# ESC_C.net
KiCad netlist of a schematic drawn in Altium Designer
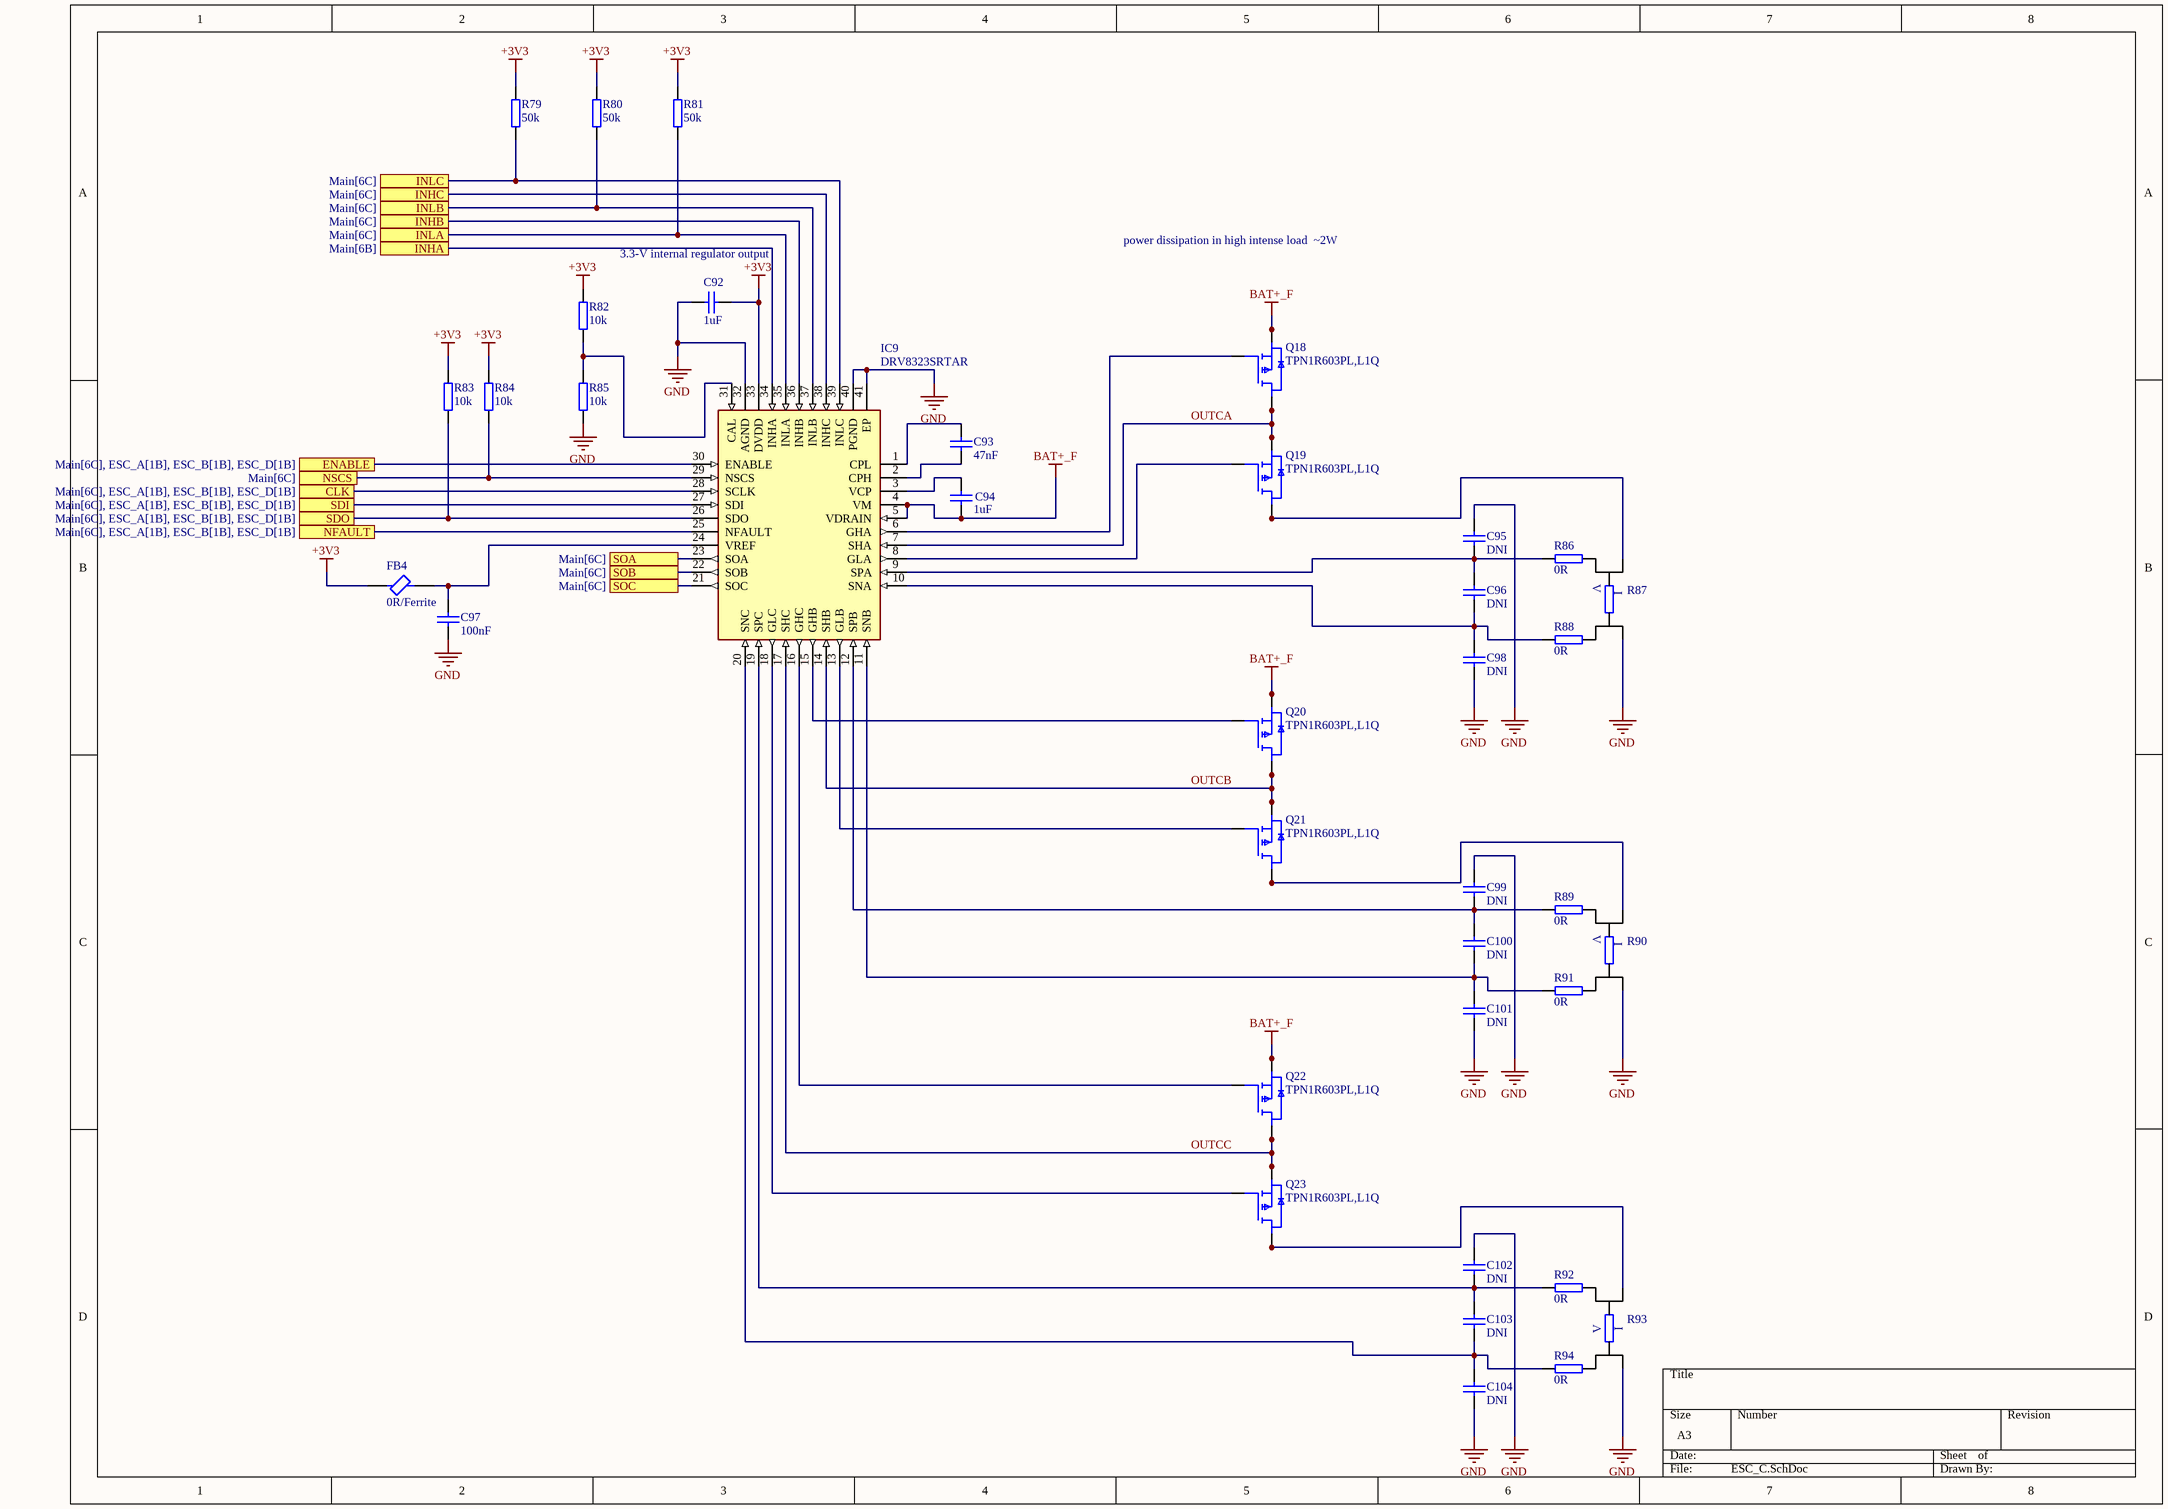
[diagram p0: ESC_C.SchDoc]

(export (version "E")
  (design (tool "Eeschema 10.0.6"))
  (components
    (comp (ref "C92")
      (value "1uF")
      (footprint "CAP0402")
      (fields
        (field (name "VOLTAGE") "50V")
        (field (name "MANUFACTURER_PART_NUMBER") "GRM155R61H105KE05J")
        (field (name "Comment") "Cap0402")
      )
      (libsource (lib "capacitorsSMD") (part "Cap0402"))
    )
    (comp (ref "C93")
      (value "47nF")
      (footprint "CAP0603")
      (description "50V")
      (fields (field (name "Comment") "Cap0603") (field (name "PUBLISHER") "Altium Limited"))
      (libsource (lib "capacitorsSMD") (part "CapSMD0603"))
    )
    (comp (ref "C94")
      (value "1uF")
      (footprint "CAP0603")
      (description "50V")
      (fields (field (name "Comment") "Cap0603") (field (name "PUBLISHER") "Altium Limited"))
      (libsource (lib "capacitorsSMD") (part "CapSMD0603"))
    )
    (comp (ref "C95")
      (value "DNI")
      (footprint "CAP0402")
      (fields (field (name "Comment") "Cap0402"))
      (libsource (lib "capacitorsSMD") (part "Cap0402"))
    )
    (comp (ref "C96")
      (value "DNI")
      (footprint "CAP0402")
      (fields (field (name "Comment") "Cap0402"))
      (libsource (lib "capacitorsSMD") (part "Cap0402"))
    )
    (comp (ref "C97")
      (value "100nF")
      (footprint "CAP0402")
      (fields
        (field (name "VOLTAGE") "50V")
        (field (name "MANUFACTURER_PART_NUMBER") "GRM155R71H104ME14D")
        (field (name "Comment") "Cap0402")
      )
      (libsource (lib "capacitorsSMD") (part "Cap0402"))
    )
    (comp (ref "C98")
      (value "DNI")
      (footprint "CAP0402")
      (fields (field (name "Comment") "Cap0402"))
      (libsource (lib "capacitorsSMD") (part "Cap0402"))
    )
    (comp (ref "C99")
      (value "DNI")
      (footprint "CAP0402")
      (fields (field (name "Comment") "Cap0402"))
      (libsource (lib "capacitorsSMD") (part "Cap0402"))
    )
    (comp (ref "C100")
      (value "DNI")
      (footprint "CAP0402")
      (fields (field (name "Comment") "Cap0402"))
      (libsource (lib "capacitorsSMD") (part "Cap0402"))
    )
    (comp (ref "C101")
      (value "DNI")
      (footprint "CAP0402")
      (fields (field (name "Comment") "Cap0402"))
      (libsource (lib "capacitorsSMD") (part "Cap0402"))
    )
    (comp (ref "C102")
      (value "DNI")
      (footprint "CAP0402")
      (fields (field (name "Comment") "Cap0402"))
      (libsource (lib "capacitorsSMD") (part "Cap0402"))
    )
    (comp (ref "C103")
      (value "DNI")
      (footprint "CAP0402")
      (fields (field (name "Comment") "Cap0402"))
      (libsource (lib "capacitorsSMD") (part "Cap0402"))
    )
    (comp (ref "C104")
      (value "DNI")
      (footprint "CAP0402")
      (fields (field (name "Comment") "Cap0402"))
      (libsource (lib "capacitorsSMD") (part "Cap0402"))
    )
    (comp (ref "FB4")
      (value "0R/Ferrite")
      (footprint "SamacSys:NFZ15SG152SN10B")
      (description "Ferrite Bead")
      (fields
        (field (name "MANUFACTURER_PART_NUMBER") "BLM15PE471SH1D")
        (field (name "MOUSER PART NUMBER") "81-BLM15PE471SH1D")
      )
      (libsource (lib "SamacSys") (part "BLM15PE471SH1D"))
    )
    (comp (ref "IC9")
      (value "DRV8323SRTAR")
      (footprint "SamacSys:QFN50P600X600X80-41N-D")
      (description "Integrated Circuit")
      (fields (field (name "MOUSER PART NUMBER") "595-DRV8323SRTAR"))
      (libsource (lib "*") (part "DRV8323SRTAR"))
    )
    (comp (ref "Q18")
      (value "TPN1R603PL,L1Q")
      (footprint "SamacSys:TPN1R603PLL1Q")
      (description "MOSFET (N-Channel)")
      (fields (field (name "MOUSER PART NUMBER") "757-TPN1R603PLL1Q"))
      (libsource (lib "SamacSys") (part "TPN1R603PL,L1Q"))
    )
    (comp (ref "Q19")
      (value "TPN1R603PL,L1Q")
      (footprint "SamacSys:TPN1R603PLL1Q")
      (description "MOSFET (N-Channel)")
      (fields (field (name "MOUSER PART NUMBER") "757-TPN1R603PLL1Q"))
      (libsource (lib "SamacSys") (part "TPN1R603PL,L1Q"))
    )
    (comp (ref "Q20")
      (value "TPN1R603PL,L1Q")
      (footprint "SamacSys:TPN1R603PLL1Q")
      (description "MOSFET (N-Channel)")
      (fields (field (name "MOUSER PART NUMBER") "757-TPN1R603PLL1Q"))
      (libsource (lib "SamacSys") (part "TPN1R603PL,L1Q"))
    )
    (comp (ref "Q21")
      (value "TPN1R603PL,L1Q")
      (footprint "SamacSys:TPN1R603PLL1Q")
      (description "MOSFET (N-Channel)")
      (fields (field (name "MOUSER PART NUMBER") "757-TPN1R603PLL1Q"))
      (libsource (lib "SamacSys") (part "TPN1R603PL,L1Q"))
    )
    (comp (ref "Q22")
      (value "TPN1R603PL,L1Q")
      (footprint "SamacSys:TPN1R603PLL1Q")
      (description "MOSFET (N-Channel)")
      (fields (field (name "MOUSER PART NUMBER") "757-TPN1R603PLL1Q"))
      (libsource (lib "SamacSys") (part "TPN1R603PL,L1Q"))
    )
    (comp (ref "Q23")
      (value "TPN1R603PL,L1Q")
      (footprint "SamacSys:TPN1R603PLL1Q")
      (description "MOSFET (N-Channel)")
      (fields (field (name "MOUSER PART NUMBER") "757-TPN1R603PLL1Q"))
      (libsource (lib "SamacSys") (part "TPN1R603PL,L1Q"))
    )
    (comp (ref "R79")
      (value "50k")
      (footprint "RES0402")
      (fields (field (name "MANUFACTURER_PART_NUMBER") "TNPW040249K9DEED") (field (name "Comment") "Res0402"))
      (libsource (lib "resistorSMD") (part "Res0402"))
    )
    (comp (ref "R80")
      (value "50k")
      (footprint "RES0402")
      (fields (field (name "MANUFACTURER_PART_NUMBER") "TNPW040249K9DEED") (field (name "Comment") "Res0402"))
      (libsource (lib "resistorSMD") (part "Res0402"))
    )
    (comp (ref "R81")
      (value "50k")
      (footprint "RES0402")
      (fields (field (name "MANUFACTURER_PART_NUMBER") "TNPW040249K9DEED") (field (name "Comment") "Res0402"))
      (libsource (lib "resistorSMD") (part "Res0402"))
    )
    (comp (ref "R82")
      (value "10k")
      (footprint "RES0402")
      (fields (field (name "MANUFACTURER_PART_NUMBER") "ERA-2AED103X") (field (name "Comment") "Res0402"))
      (libsource (lib "resistorSMD") (part "Res0402"))
    )
    (comp (ref "R83")
      (value "10k")
      (footprint "RES0402")
      (fields (field (name "MANUFACTURER_PART_NUMBER") "ERA-2AED103X") (field (name "Comment") "Res0402"))
      (libsource (lib "resistorSMD") (part "Res0402"))
    )
    (comp (ref "R84")
      (value "10k")
      (footprint "RES0402")
      (fields (field (name "MANUFACTURER_PART_NUMBER") "ERA-2AED103X") (field (name "Comment") "Res0402"))
      (libsource (lib "resistorSMD") (part "Res0402"))
    )
    (comp (ref "R85")
      (value "10k")
      (footprint "RES0402")
      (fields (field (name "MANUFACTURER_PART_NUMBER") "ERA-2AED103X") (field (name "Comment") "Res0402"))
      (libsource (lib "resistorSMD") (part "Res0402"))
    )
    (comp (ref "R86")
      (value "0R")
      (footprint "RES0402")
      (fields (field (name "MANUFACTURER_PART_NUMBER") "RCA04020000ZSED") (field (name "Comment") "Res0402"))
      (libsource (lib "resistorSMD") (part "Res0402"))
    )
    (comp (ref "R87")
      (value "WSK12161L000FEA")
      (footprint "SamacSys:WSK12161L000FEA")
      (description "Resistor")
      (fields
        (field (name "MANUFACTURER_PART_NUMBER") "WSK1216L5000FEA")
        (field (name "MOUSER PART NUMBER") "71-WSK1216L5000FEA")
      )
      (libsource (lib "SamacSys") (part "WSK1216L5000FEA"))
    )
    (comp (ref "R88")
      (value "0R")
      (footprint "RES0402")
      (fields (field (name "MANUFACTURER_PART_NUMBER") "RCA04020000ZSED") (field (name "Comment") "Res0402"))
      (libsource (lib "resistorSMD") (part "Res0402"))
    )
    (comp (ref "R89")
      (value "0R")
      (footprint "RES0402")
      (fields (field (name "MANUFACTURER_PART_NUMBER") "RCA04020000ZSED") (field (name "Comment") "Res0402"))
      (libsource (lib "resistorSMD") (part "Res0402"))
    )
    (comp (ref "R90")
      (value "WSK12161L000FEA")
      (footprint "SamacSys:WSK12161L000FEA")
      (description "Resistor")
      (fields
        (field (name "MANUFACTURER_PART_NUMBER") "WSK1216L5000FEA")
        (field (name "MOUSER PART NUMBER") "71-WSK1216L5000FEA")
      )
      (libsource (lib "SamacSys") (part "WSK1216L5000FEA"))
    )
    (comp (ref "R91")
      (value "0R")
      (footprint "RES0402")
      (fields (field (name "MANUFACTURER_PART_NUMBER") "RCA04020000ZSED") (field (name "Comment") "Res0402"))
      (libsource (lib "resistorSMD") (part "Res0402"))
    )
    (comp (ref "R92")
      (value "0R")
      (footprint "RES0402")
      (fields (field (name "MANUFACTURER_PART_NUMBER") "RCA04020000ZSED") (field (name "Comment") "Res0402"))
      (libsource (lib "resistorSMD") (part "Res0402"))
    )
    (comp (ref "R93")
      (value "WSK12161L000FEA")
      (footprint "SamacSys:WSK12161L000FEA")
      (description "Resistor")
      (fields
        (field (name "MANUFACTURER_PART_NUMBER") "WSK1216L5000FEA")
        (field (name "MOUSER PART NUMBER") "71-WSK1216L5000FEA")
      )
      (libsource (lib "SamacSys") (part "WSK1216L5000FEA"))
    )
    (comp (ref "R94")
      (value "0R")
      (footprint "RES0402")
      (fields (field (name "MANUFACTURER_PART_NUMBER") "RCA04020000ZSED") (field (name "Comment") "Res0402"))
      (libsource (lib "resistorSMD") (part "Res0402"))
    )
  )
  (nets
    (net (code "1") (name "+3V3") (class "Default")
      (node (ref "C92") (pin "2") (pinfunction "2_2") (pintype "passive"))
      (node (ref "FB4") (pin "1") (pinfunction "1_1") (pintype "passive"))
      (node (ref "IC9") (pin "33") (pinfunction "DVDD_33") (pintype "power_in"))
      (node (ref "R79") (pin "2") (pinfunction "2_2") (pintype "passive"))
      (node (ref "R80") (pin "2") (pinfunction "2_2") (pintype "passive"))
      (node (ref "R81") (pin "2") (pinfunction "2_2") (pintype "passive"))
      (node (ref "R82") (pin "2") (pinfunction "2_2") (pintype "passive"))
      (node (ref "R83") (pin "2") (pinfunction "2_2") (pintype "passive"))
      (node (ref "R84") (pin "2") (pinfunction "2_2") (pintype "passive"))
    )
    (net (code "2") (name "/CLK") (class "Default")
      (node (ref "IC9") (pin "28") (pinfunction "SCLK_28") (pintype "input"))
    )
    (net (code "3") (name "/ENABLE") (class "Default")
      (node (ref "IC9") (pin "30") (pinfunction "ENABLE_30") (pintype "input"))
    )
    (net (code "4") (name "/INHA") (class "Default")
      (node (ref "IC9") (pin "34") (pinfunction "INHA_34") (pintype "input"))
    )
    (net (code "5") (name "/INHB") (class "Default")
      (node (ref "IC9") (pin "36") (pinfunction "INHB_36") (pintype "input"))
    )
    (net (code "6") (name "/INHC") (class "Default")
      (node (ref "IC9") (pin "38") (pinfunction "INHC_38") (pintype "input"))
    )
    (net (code "7") (name "/INLA") (class "Default")
      (node (ref "IC9") (pin "35") (pinfunction "INLA_35") (pintype "input"))
      (node (ref "R81") (pin "1") (pinfunction "1_1") (pintype "passive"))
    )
    (net (code "8") (name "/INLB") (class "Default")
      (node (ref "IC9") (pin "37") (pinfunction "INLB_37") (pintype "input"))
      (node (ref "R80") (pin "1") (pinfunction "1_1") (pintype "passive"))
    )
    (net (code "9") (name "/INLC") (class "Default")
      (node (ref "IC9") (pin "39") (pinfunction "INLC_39") (pintype "input"))
      (node (ref "R79") (pin "1") (pinfunction "1_1") (pintype "passive"))
    )
    (net (code "10") (name "/NFAULT") (class "Default")
      (node (ref "IC9") (pin "25") (pinfunction "NFAULT_25") (pintype "passive"))
    )
    (net (code "11") (name "/NSCS") (class "Default")
      (node (ref "IC9") (pin "29") (pinfunction "NSCS_29") (pintype "input"))
      (node (ref "R84") (pin "1") (pinfunction "1_1") (pintype "passive"))
    )
    (net (code "12") (name "/OUTCA") (class "Default")
      (node (ref "IC9") (pin "7") (pinfunction "SHA_7") (pintype "input"))
      (node (ref "Q18") (pin "5") (pinfunction "D_1_5") (pintype "passive"))
      (node (ref "Q18") (pin "6") (pinfunction "D_2_6") (pintype "passive"))
      (node (ref "Q18") (pin "7") (pinfunction "D_3_7") (pintype "passive"))
      (node (ref "Q18") (pin "8") (pinfunction "D_4_8") (pintype "passive"))
      (node (ref "Q18") (pin "9") (pinfunction "D_4_9") (pintype "passive"))
      (node (ref "Q19") (pin "1") (pinfunction "S_1_1") (pintype "passive"))
      (node (ref "Q19") (pin "2") (pinfunction "S_2_2") (pintype "passive"))
      (node (ref "Q19") (pin "3") (pinfunction "S_3_3") (pintype "passive"))
    )
    (net (code "13") (name "/OUTCB") (class "Default")
      (node (ref "IC9") (pin "14") (pinfunction "SHB_14") (pintype "input"))
      (node (ref "Q20") (pin "5") (pinfunction "D_1_5") (pintype "passive"))
      (node (ref "Q20") (pin "6") (pinfunction "D_2_6") (pintype "passive"))
      (node (ref "Q20") (pin "7") (pinfunction "D_3_7") (pintype "passive"))
      (node (ref "Q20") (pin "8") (pinfunction "D_4_8") (pintype "passive"))
      (node (ref "Q20") (pin "9") (pinfunction "D_4_9") (pintype "passive"))
      (node (ref "Q21") (pin "1") (pinfunction "S_1_1") (pintype "passive"))
      (node (ref "Q21") (pin "2") (pinfunction "S_2_2") (pintype "passive"))
      (node (ref "Q21") (pin "3") (pinfunction "S_3_3") (pintype "passive"))
    )
    (net (code "14") (name "/OUTCC") (class "Default")
      (node (ref "IC9") (pin "17") (pinfunction "SHC_17") (pintype "input"))
      (node (ref "Q22") (pin "5") (pinfunction "D_1_5") (pintype "passive"))
      (node (ref "Q22") (pin "6") (pinfunction "D_2_6") (pintype "passive"))
      (node (ref "Q22") (pin "7") (pinfunction "D_3_7") (pintype "passive"))
      (node (ref "Q22") (pin "8") (pinfunction "D_4_8") (pintype "passive"))
      (node (ref "Q22") (pin "9") (pinfunction "D_4_9") (pintype "passive"))
      (node (ref "Q23") (pin "1") (pinfunction "S_1_1") (pintype "passive"))
      (node (ref "Q23") (pin "2") (pinfunction "S_2_2") (pintype "passive"))
      (node (ref "Q23") (pin "3") (pinfunction "S_3_3") (pintype "passive"))
    )
    (net (code "15") (name "/SDI") (class "Default")
      (node (ref "IC9") (pin "27") (pinfunction "SDI_27") (pintype "input"))
    )
    (net (code "16") (name "/SDO") (class "Default")
      (node (ref "IC9") (pin "26") (pinfunction "SDO_26") (pintype "passive"))
      (node (ref "R83") (pin "1") (pinfunction "1_1") (pintype "passive"))
    )
    (net (code "17") (name "/SOA") (class "Default")
      (node (ref "IC9") (pin "23") (pinfunction "SOA_23") (pintype "output"))
    )
    (net (code "18") (name "/SOB") (class "Default")
      (node (ref "IC9") (pin "22") (pinfunction "SOB_22") (pintype "output"))
    )
    (net (code "19") (name "/SOC") (class "Default")
      (node (ref "IC9") (pin "21") (pinfunction "SOC_21") (pintype "output"))
    )
    (net (code "20") (name "BAT+_F") (class "Default")
      (node (ref "C94") (pin "1") (pinfunction "1_1") (pintype "passive"))
      (node (ref "IC9") (pin "4") (pinfunction "VM_4") (pintype "power_in"))
      (node (ref "IC9") (pin "5") (pinfunction "VDRAIN_5") (pintype "input"))
      (node (ref "Q18") (pin "1") (pinfunction "S_1_1") (pintype "passive"))
      (node (ref "Q18") (pin "2") (pinfunction "S_2_2") (pintype "passive"))
      (node (ref "Q18") (pin "3") (pinfunction "S_3_3") (pintype "passive"))
      (node (ref "Q20") (pin "1") (pinfunction "S_1_1") (pintype "passive"))
      (node (ref "Q20") (pin "2") (pinfunction "S_2_2") (pintype "passive"))
      (node (ref "Q20") (pin "3") (pinfunction "S_3_3") (pintype "passive"))
      (node (ref "Q22") (pin "1") (pinfunction "S_1_1") (pintype "passive"))
      (node (ref "Q22") (pin "2") (pinfunction "S_2_2") (pintype "passive"))
      (node (ref "Q22") (pin "3") (pinfunction "S_3_3") (pintype "passive"))
    )
    (net (code "21") (name "GND") (class "Default")
      (node (ref "C101") (pin "2") (pinfunction "2_2") (pintype "passive"))
      (node (ref "C102") (pin "1") (pinfunction "1_1") (pintype "passive"))
      (node (ref "C104") (pin "2") (pinfunction "2_2") (pintype "passive"))
      (node (ref "C92") (pin "1") (pinfunction "1_1") (pintype "passive"))
      (node (ref "C95") (pin "1") (pinfunction "1_1") (pintype "passive"))
      (node (ref "C97") (pin "1") (pinfunction "1_1") (pintype "passive"))
      (node (ref "C98") (pin "2") (pinfunction "2_2") (pintype "passive"))
      (node (ref "C99") (pin "1") (pinfunction "1_1") (pintype "passive"))
      (node (ref "IC9") (pin "32") (pinfunction "AGND_32") (pintype "power_in"))
      (node (ref "IC9") (pin "40") (pinfunction "PGND_40") (pintype "power_in"))
      (node (ref "IC9") (pin "41") (pinfunction "EP_41") (pintype "power_in"))
      (node (ref "R85") (pin "1") (pinfunction "1_1") (pintype "passive"))
      (node (ref "R87") (pin "4") (pinfunction "4_4") (pintype "passive"))
      (node (ref "R90") (pin "4") (pinfunction "4_4") (pintype "passive"))
      (node (ref "R93") (pin "1") (pinfunction "1_1") (pintype "passive"))
    )
    (net (code "22") (name "Net-(IC9-CAL)") (class "Default")
      (node (ref "IC9") (pin "31") (pinfunction "CAL_31") (pintype "input"))
      (node (ref "R82") (pin "1") (pinfunction "1_1") (pintype "passive"))
      (node (ref "R85") (pin "2") (pinfunction "2_2") (pintype "passive"))
    )
    (net (code "23") (name "Net-(IC9-CPH)") (class "Default")
      (node (ref "C93") (pin "1") (pinfunction "1_1") (pintype "passive"))
      (node (ref "IC9") (pin "2") (pinfunction "CPH_2") (pintype "power_in"))
    )
    (net (code "24") (name "Net-(IC9-CPL)") (class "Default")
      (node (ref "C93") (pin "2") (pinfunction "2_2") (pintype "passive"))
      (node (ref "IC9") (pin "1") (pinfunction "CPL_1") (pintype "power_in"))
    )
    (net (code "25") (name "Net-(IC9-GHA)") (class "Default")
      (node (ref "IC9") (pin "6") (pinfunction "GHA_6") (pintype "output"))
      (node (ref "Q18") (pin "4") (pinfunction "G_4") (pintype "passive"))
    )
    (net (code "26") (name "Net-(IC9-GHB)") (class "Default")
      (node (ref "IC9") (pin "15") (pinfunction "GHB_15") (pintype "output"))
      (node (ref "Q20") (pin "4") (pinfunction "G_4") (pintype "passive"))
    )
    (net (code "27") (name "Net-(IC9-GHC)") (class "Default")
      (node (ref "IC9") (pin "16") (pinfunction "GHC_16") (pintype "output"))
      (node (ref "Q22") (pin "4") (pinfunction "G_4") (pintype "passive"))
    )
    (net (code "28") (name "Net-(IC9-GLA)") (class "Default")
      (node (ref "IC9") (pin "8") (pinfunction "GLA_8") (pintype "output"))
      (node (ref "Q19") (pin "4") (pinfunction "G_4") (pintype "passive"))
    )
    (net (code "29") (name "Net-(IC9-GLB)") (class "Default")
      (node (ref "IC9") (pin "13") (pinfunction "GLB_13") (pintype "output"))
      (node (ref "Q21") (pin "4") (pinfunction "G_4") (pintype "passive"))
    )
    (net (code "30") (name "Net-(IC9-GLC)") (class "Default")
      (node (ref "IC9") (pin "18") (pinfunction "GLC_18") (pintype "output"))
      (node (ref "Q23") (pin "4") (pinfunction "G_4") (pintype "passive"))
    )
    (net (code "31") (name "Net-(IC9-SNA)") (class "Default")
      (node (ref "C96") (pin "2") (pinfunction "2_2") (pintype "passive"))
      (node (ref "C98") (pin "1") (pinfunction "1_1") (pintype "passive"))
      (node (ref "IC9") (pin "10") (pinfunction "SNA_10") (pintype "input"))
      (node (ref "R88") (pin "1") (pinfunction "1_1") (pintype "passive"))
    )
    (net (code "32") (name "Net-(IC9-SNB)") (class "Default")
      (node (ref "C100") (pin "2") (pinfunction "2_2") (pintype "passive"))
      (node (ref "C101") (pin "1") (pinfunction "1_1") (pintype "passive"))
      (node (ref "IC9") (pin "11") (pinfunction "SNB_11") (pintype "input"))
      (node (ref "R91") (pin "1") (pinfunction "1_1") (pintype "passive"))
    )
    (net (code "33") (name "Net-(IC9-SNC)") (class "Default")
      (node (ref "C103") (pin "2") (pinfunction "2_2") (pintype "passive"))
      (node (ref "C104") (pin "1") (pinfunction "1_1") (pintype "passive"))
      (node (ref "IC9") (pin "20") (pinfunction "SNC_20") (pintype "input"))
      (node (ref "R94") (pin "1") (pinfunction "1_1") (pintype "passive"))
    )
    (net (code "34") (name "Net-(IC9-SPA)") (class "Default")
      (node (ref "C95") (pin "2") (pinfunction "2_2") (pintype "passive"))
      (node (ref "C96") (pin "1") (pinfunction "1_1") (pintype "passive"))
      (node (ref "IC9") (pin "9") (pinfunction "SPA_9") (pintype "input"))
      (node (ref "R86") (pin "1") (pinfunction "1_1") (pintype "passive"))
    )
    (net (code "35") (name "Net-(IC9-SPB)") (class "Default")
      (node (ref "C100") (pin "1") (pinfunction "1_1") (pintype "passive"))
      (node (ref "C99") (pin "2") (pinfunction "2_2") (pintype "passive"))
      (node (ref "IC9") (pin "12") (pinfunction "SPB_12") (pintype "input"))
      (node (ref "R89") (pin "1") (pinfunction "1_1") (pintype "passive"))
    )
    (net (code "36") (name "Net-(IC9-SPC)") (class "Default")
      (node (ref "C102") (pin "2") (pinfunction "2_2") (pintype "passive"))
      (node (ref "C103") (pin "1") (pinfunction "1_1") (pintype "passive"))
      (node (ref "IC9") (pin "19") (pinfunction "SPC_19") (pintype "input"))
      (node (ref "R92") (pin "1") (pinfunction "1_1") (pintype "passive"))
    )
    (net (code "37") (name "Net-(IC9-VCP)") (class "Default")
      (node (ref "C94") (pin "2") (pinfunction "2_2") (pintype "passive"))
      (node (ref "IC9") (pin "3") (pinfunction "VCP_3") (pintype "power_in"))
    )
    (net (code "38") (name "Net-(IC9-VREF)") (class "Default")
      (node (ref "C97") (pin "2") (pinfunction "2_2") (pintype "passive"))
      (node (ref "FB4") (pin "2") (pinfunction "2_2") (pintype "passive"))
      (node (ref "IC9") (pin "24") (pinfunction "VREF_24") (pintype "power_in"))
    )
    (net (code "39") (name "Net-(Q19-D_1)") (class "Default")
      (node (ref "Q19") (pin "5") (pinfunction "D_1_5") (pintype "passive"))
      (node (ref "Q19") (pin "6") (pinfunction "D_2_6") (pintype "passive"))
      (node (ref "Q19") (pin "7") (pinfunction "D_3_7") (pintype "passive"))
      (node (ref "Q19") (pin "8") (pinfunction "D_4_8") (pintype "passive"))
      (node (ref "Q19") (pin "9") (pinfunction "D_4_9") (pintype "passive"))
      (node (ref "R87") (pin "1") (pinfunction "1_1") (pintype "passive"))
    )
    (net (code "40") (name "Net-(Q21-D_1)") (class "Default")
      (node (ref "Q21") (pin "5") (pinfunction "D_1_5") (pintype "passive"))
      (node (ref "Q21") (pin "6") (pinfunction "D_2_6") (pintype "passive"))
      (node (ref "Q21") (pin "7") (pinfunction "D_3_7") (pintype "passive"))
      (node (ref "Q21") (pin "8") (pinfunction "D_4_8") (pintype "passive"))
      (node (ref "Q21") (pin "9") (pinfunction "D_4_9") (pintype "passive"))
      (node (ref "R90") (pin "1") (pinfunction "1_1") (pintype "passive"))
    )
    (net (code "41") (name "Net-(Q23-D_1)") (class "Default")
      (node (ref "Q23") (pin "5") (pinfunction "D_1_5") (pintype "passive"))
      (node (ref "Q23") (pin "6") (pinfunction "D_2_6") (pintype "passive"))
      (node (ref "Q23") (pin "7") (pinfunction "D_3_7") (pintype "passive"))
      (node (ref "Q23") (pin "8") (pinfunction "D_4_8") (pintype "passive"))
      (node (ref "Q23") (pin "9") (pinfunction "D_4_9") (pintype "passive"))
      (node (ref "R93") (pin "4") (pinfunction "4_4") (pintype "passive"))
    )
    (net (code "42") (name "Net-(R86-Pad2)") (class "Default")
      (node (ref "R86") (pin "2") (pinfunction "2_2") (pintype "passive"))
      (node (ref "R87") (pin "2") (pinfunction "2_2") (pintype "passive"))
    )
    (net (code "43") (name "Net-(R87-Pad3)") (class "Default")
      (node (ref "R87") (pin "3") (pinfunction "3_3") (pintype "passive"))
      (node (ref "R88") (pin "2") (pinfunction "2_2") (pintype "passive"))
    )
    (net (code "44") (name "Net-(R89-Pad2)") (class "Default")
      (node (ref "R89") (pin "2") (pinfunction "2_2") (pintype "passive"))
      (node (ref "R90") (pin "2") (pinfunction "2_2") (pintype "passive"))
    )
    (net (code "45") (name "Net-(R90-Pad3)") (class "Default")
      (node (ref "R90") (pin "3") (pinfunction "3_3") (pintype "passive"))
      (node (ref "R91") (pin "2") (pinfunction "2_2") (pintype "passive"))
    )
    (net (code "46") (name "Net-(R92-Pad2)") (class "Default")
      (node (ref "R92") (pin "2") (pinfunction "2_2") (pintype "passive"))
      (node (ref "R93") (pin "3") (pinfunction "3_3") (pintype "passive"))
    )
    (net (code "47") (name "Net-(R93-Pad2)") (class "Default")
      (node (ref "R93") (pin "2") (pinfunction "2_2") (pintype "passive"))
      (node (ref "R94") (pin "2") (pinfunction "2_2") (pintype "passive"))
    )
  )
)
